# PhatStats_Slim_Enclosure_QTPY_PCB_v0_93.net
KiCad netlist of a schematic drawn in EAGLE
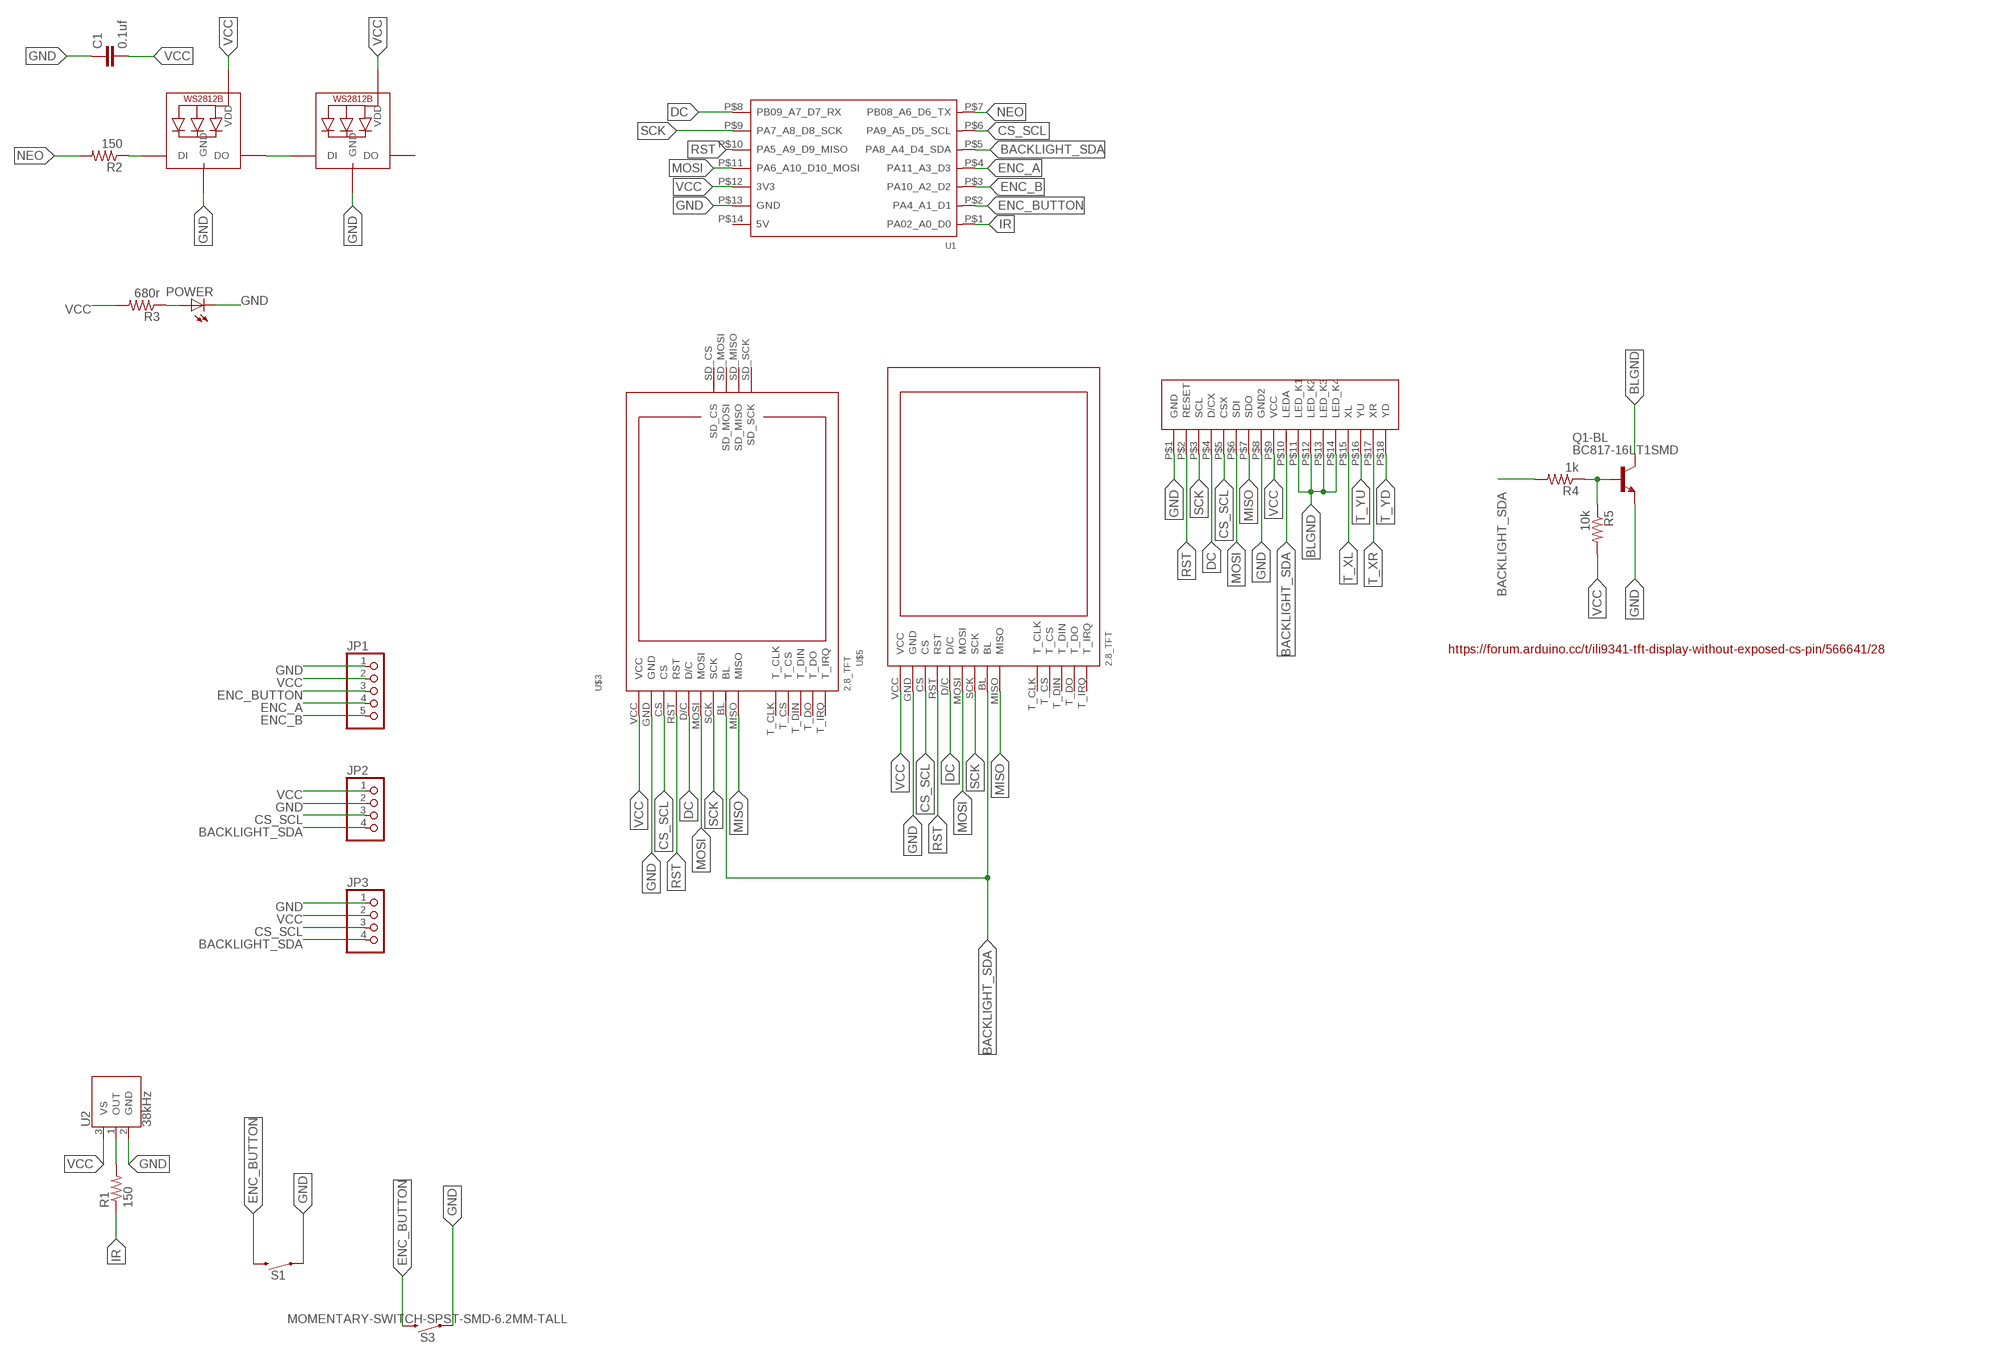
[diagram p0: schematic, sheet 1]

(export (version "E")
  (design (tool "Eeschema 10.0.6"))
  (components
    (comp (ref "0")
      (value "ILI9341-2.8")
      (footprint "eagle-import:ILI9341-2.8")
      (libsource (lib "eagle-import") (part "ILI9341-2.8"))
    )
    (comp (ref "C1")
      (value "0.1uf")
      (footprint "eagle-import:C1206")
      (libsource (lib "eagle-import") (part "C-EUC1206"))
    )
    (comp (ref "JP1")
      (value "PINHD-1X5")
      (footprint "eagle-import:1X05")
      (libsource (lib "eagle-import") (part "PINHD-1X5"))
    )
    (comp (ref "JP2")
      (value "PINHD-1X4")
      (footprint "eagle-import:1X04")
      (libsource (lib "eagle-import") (part "PINHD-1X4"))
    )
    (comp (ref "JP3")
      (value "PINHD-1X4")
      (footprint "eagle-import:1X04")
      (libsource (lib "eagle-import") (part "PINHD-1X4"))
    )
    (comp (ref "NEO1")
      (value "WS2812B5050")
      (footprint "eagle-import:WS2812B")
      (libsource (lib "eagle-import") (part "WS2812B5050"))
    )
    (comp (ref "NEO2")
      (value "WS2812B5050")
      (footprint "eagle-import:WS2812B")
      (libsource (lib "eagle-import") (part "WS2812B5050"))
    )
    (comp (ref "POWER")
      (value "LEDCHIPLED_1206")
      (footprint "eagle-import:CHIPLED_1206")
      (libsource (lib "eagle-import") (part "LEDCHIPLED_1206"))
    )
    (comp (ref "Q1-BL")
      (value "BC817-16LT1SMD")
      (footprint "eagle-import:SOT23-BEC")
      (libsource (lib "eagle-import") (part "BC817SMD-16LT1"))
    )
    (comp (ref "R1")
      (value "150")
      (footprint "eagle-import:M1206")
      (libsource (lib "eagle-import") (part "R-US_M1206"))
    )
    (comp (ref "R2")
      (value "150")
      (footprint "eagle-import:M1206")
      (libsource (lib "eagle-import") (part "R-US_M1206"))
    )
    (comp (ref "R3")
      (value "680r")
      (footprint "eagle-import:M1206")
      (libsource (lib "eagle-import") (part "R-US_M1206"))
    )
    (comp (ref "R4")
      (value "1k")
      (footprint "eagle-import:M1206")
      (libsource (lib "eagle-import") (part "R-US_M1206"))
    )
    (comp (ref "R5")
      (value "10k")
      (footprint "eagle-import:M1206")
      (libsource (lib "eagle-import") (part "R-US_M1206"))
    )
    (comp (ref "S1")
      (value "MOMENTARY-SWITCH-SPST-PTH-6.0MM")
      (footprint "eagle-import:TACTILE_SWITCH_PTH_6.0MM")
      (libsource (lib "eagle-import") (part "MOMENTARY-SWITCH-SPST-PTH-6.0MM"))
    )
    (comp (ref "S3")
      (value "MOMENTARY-SWITCH-SPST-SMD-6.2MM-TALL")
      (footprint "eagle-import:TACTILE_SWITCH_SMD_6.2MM_TALL")
      (libsource (lib "eagle-import") (part "MOMENTARY-SWITCH-SPST-SMD-6.2MM-TALL"))
    )
    (comp (ref "U$3")
      (value "2.8_TFT")
      (footprint "eagle-import:2.8_TFT")
      (libsource (lib "eagle-import") (part "2.8_TFT"))
    )
    (comp (ref "U$5")
      (value "2.8_TFT")
      (footprint "eagle-import:2.8_TFT")
      (libsource (lib "eagle-import") (part "TML_ili9341-2.8_tft-display_PinHeader only_2.8_TFT"))
    )
    (comp (ref "U1")
      (value "MOUDLE-SEEEDUINO-XIAO")
      (footprint "eagle-import:MOUDLE14P-2.54-21X17.8MM")
      (libsource (lib "eagle-import") (part "MOUDLE-SEEEDUINO-XIAO"))
    )
    (comp (ref "U2")
      (value "38kHz")
      (footprint "eagle-import:TSOP382")
      (libsource (lib "eagle-import") (part "TSOP38238"))
    )
  )
  (nets
    (net (code "1") (name "BACKLIGHT_SDA") (class "Default")
      (node (ref "0") (pin "P$10") (pinfunction "LEDA_P$10") (pintype "bidirectional"))
      (node (ref "JP2") (pin "4") (pinfunction "4_4") (pintype "passive"))
      (node (ref "JP3") (pin "4") (pinfunction "4_4") (pintype "passive"))
      (node (ref "R4") (pin "2") (pinfunction "2_2") (pintype "passive"))
      (node (ref "U$3") (pin "BL") (pinfunction "BL_BL") (pintype "bidirectional"))
      (node (ref "U$5") (pin "BL") (pinfunction "BL_BL") (pintype "bidirectional"))
      (node (ref "U1") (pin "P$5") (pinfunction "PA8_A4_D4_SDA_P$5") (pintype "bidirectional"))
    )
    (net (code "2") (name "BLGND") (class "Default")
      (node (ref "0") (pin "P$11") (pinfunction "LED_K1_P$11") (pintype "bidirectional"))
      (node (ref "0") (pin "P$12") (pinfunction "LED_K2_P$12") (pintype "bidirectional"))
      (node (ref "0") (pin "P$13") (pinfunction "LED_K3_P$13") (pintype "bidirectional"))
      (node (ref "0") (pin "P$14") (pinfunction "LED_K4_P$14") (pintype "bidirectional"))
      (node (ref "Q1-BL") (pin "C") (pinfunction "C_C") (pintype "passive"))
    )
    (net (code "3") (name "CS_SCL") (class "Default")
      (node (ref "0") (pin "P$5") (pinfunction "CSX_P$5") (pintype "bidirectional"))
      (node (ref "JP2") (pin "3") (pinfunction "3_3") (pintype "passive"))
      (node (ref "JP3") (pin "3") (pinfunction "3_3") (pintype "passive"))
      (node (ref "U$3") (pin "CS") (pinfunction "CS_CS") (pintype "bidirectional"))
      (node (ref "U$5") (pin "CS") (pinfunction "CS_CS") (pintype "bidirectional"))
      (node (ref "U1") (pin "P$6") (pinfunction "PA9_A5_D5_SCL_P$6") (pintype "bidirectional"))
    )
    (net (code "4") (name "DC") (class "Default")
      (node (ref "0") (pin "P$4") (pinfunction "D/CX_P$4") (pintype "bidirectional"))
      (node (ref "U$3") (pin "D/C") (pinfunction "D/C_D/C") (pintype "bidirectional"))
      (node (ref "U$5") (pin "D/C") (pinfunction "D/C_D/C") (pintype "bidirectional"))
      (node (ref "U1") (pin "P$8") (pinfunction "PB09_A7_D7_RX_P$8") (pintype "bidirectional"))
    )
    (net (code "5") (name "ENC_A") (class "Default")
      (node (ref "JP1") (pin "4") (pinfunction "4_4") (pintype "passive"))
      (node (ref "U1") (pin "P$4") (pinfunction "PA11_A3_D3_P$4") (pintype "bidirectional"))
    )
    (net (code "6") (name "ENC_B") (class "Default")
      (node (ref "JP1") (pin "5") (pinfunction "5_5") (pintype "passive"))
      (node (ref "U1") (pin "P$3") (pinfunction "PA10_A2_D2_P$3") (pintype "bidirectional"))
    )
    (net (code "7") (name "ENC_BUTTON") (class "Default")
      (node (ref "JP1") (pin "3") (pinfunction "3_3") (pintype "passive"))
      (node (ref "S1") (pin "3") (pinfunction "2_3") (pintype "passive"))
      (node (ref "S3") (pin "B2") (pinfunction "2_B2") (pintype "passive"))
      (node (ref "U1") (pin "P$2") (pinfunction "PA4_A1_D1_P$2") (pintype "bidirectional"))
    )
    (net (code "8") (name "GND") (class "Default")
      (node (ref "0") (pin "P$1") (pinfunction "GND_P$1") (pintype "bidirectional"))
      (node (ref "0") (pin "P$8") (pinfunction "GND2_P$8") (pintype "bidirectional"))
      (node (ref "C1") (pin "1") (pinfunction "1_1") (pintype "passive"))
      (node (ref "JP1") (pin "1") (pinfunction "1_1") (pintype "passive"))
      (node (ref "JP2") (pin "2") (pinfunction "2_2") (pintype "passive"))
      (node (ref "JP3") (pin "1") (pinfunction "1_1") (pintype "passive"))
      (node (ref "NEO1") (pin "3-GND") (pinfunction "GND_3-GND") (pintype "power_in"))
      (node (ref "NEO2") (pin "3-GND") (pinfunction "GND_3-GND") (pintype "power_in"))
      (node (ref "POWER") (pin "C") (pinfunction "C_C") (pintype "passive"))
      (node (ref "Q1-BL") (pin "E") (pinfunction "E_E") (pintype "passive"))
      (node (ref "S1") (pin "1") (pinfunction "1_1") (pintype "passive"))
      (node (ref "S3") (pin "A2") (pinfunction "1_A2") (pintype "passive"))
      (node (ref "U$3") (pin "GND") (pinfunction "GND_GND") (pintype "bidirectional"))
      (node (ref "U$5") (pin "GND") (pinfunction "GND_GND") (pintype "bidirectional"))
      (node (ref "U1") (pin "P$13") (pinfunction "GND_P$13") (pintype "bidirectional"))
      (node (ref "U2") (pin "2") (pinfunction "GND_2") (pintype "bidirectional"))
    )
    (net (code "9") (name "IR") (class "Default")
      (node (ref "R1") (pin "1") (pinfunction "1_1") (pintype "passive"))
      (node (ref "U1") (pin "P$1") (pinfunction "PA02_A0_D0_P$1") (pintype "bidirectional"))
    )
    (net (code "10") (name "MISO") (class "Default")
      (node (ref "0") (pin "P$7") (pinfunction "SDO_P$7") (pintype "bidirectional"))
      (node (ref "U$3") (pin "MISO") (pinfunction "MISO_MISO") (pintype "bidirectional"))
      (node (ref "U$5") (pin "MISO") (pinfunction "MISO_MISO") (pintype "bidirectional"))
    )
    (net (code "11") (name "MOSI") (class "Default")
      (node (ref "0") (pin "P$6") (pinfunction "SDI_P$6") (pintype "bidirectional"))
      (node (ref "U$3") (pin "MOSI") (pinfunction "MOSI_MOSI") (pintype "bidirectional"))
      (node (ref "U$5") (pin "MOSI") (pinfunction "MOSI_MOSI") (pintype "bidirectional"))
      (node (ref "U1") (pin "P$11") (pinfunction "PA6_A10_D10_MOSI_P$11") (pintype "bidirectional"))
    )
    (net (code "12") (name "NEO") (class "Default")
      (node (ref "R2") (pin "2") (pinfunction "2_2") (pintype "passive"))
      (node (ref "U1") (pin "P$7") (pinfunction "PB08_A6_D6_TX_P$7") (pintype "bidirectional"))
    )
    (net (code "13") (name "Net-(NEO1-DI)") (class "Default")
      (node (ref "NEO1") (pin "4-DIN") (pinfunction "DI_4-DIN") (pintype "input"))
      (node (ref "R2") (pin "1") (pinfunction "1_1") (pintype "passive"))
    )
    (net (code "14") (name "Net-(NEO1-DO)") (class "Default")
      (node (ref "NEO1") (pin "2-DOUT") (pinfunction "DO_2-DOUT") (pintype "output"))
      (node (ref "NEO2") (pin "4-DIN") (pinfunction "DI_4-DIN") (pintype "input"))
    )
    (net (code "15") (name "Net-(POWER-PadA)") (class "Default")
      (node (ref "POWER") (pin "A") (pinfunction "A_A") (pintype "passive"))
      (node (ref "R3") (pin "1") (pinfunction "1_1") (pintype "passive"))
    )
    (net (code "16") (name "Net-(Q1-BL-PadB)") (class "Default")
      (node (ref "Q1-BL") (pin "B") (pinfunction "B_B") (pintype "passive"))
      (node (ref "R4") (pin "1") (pinfunction "1_1") (pintype "passive"))
      (node (ref "R5") (pin "1") (pinfunction "1_1") (pintype "passive"))
    )
    (net (code "17") (name "Net-(U2-OUT)") (class "Default")
      (node (ref "R1") (pin "2") (pinfunction "2_2") (pintype "passive"))
      (node (ref "U2") (pin "1") (pinfunction "OUT_1") (pintype "bidirectional"))
    )
    (net (code "18") (name "RST") (class "Default")
      (node (ref "0") (pin "P$2") (pinfunction "RESET_P$2") (pintype "bidirectional"))
      (node (ref "U$3") (pin "RST") (pinfunction "RST_RST") (pintype "bidirectional"))
      (node (ref "U$5") (pin "RST") (pinfunction "RST_RST") (pintype "bidirectional"))
      (node (ref "U1") (pin "P$10") (pinfunction "PA5_A9_D9_MISO_P$10") (pintype "bidirectional"))
    )
    (net (code "19") (name "SCK") (class "Default")
      (node (ref "0") (pin "P$3") (pinfunction "SCL_P$3") (pintype "bidirectional"))
      (node (ref "U$3") (pin "SCK") (pinfunction "SCK_SCK") (pintype "bidirectional"))
      (node (ref "U$5") (pin "SCK") (pinfunction "SCK_SCK") (pintype "bidirectional"))
      (node (ref "U1") (pin "P$9") (pinfunction "PA7_A8_D8_SCK_P$9") (pintype "bidirectional"))
    )
    (net (code "20") (name "T_XL") (class "Default")
      (node (ref "0") (pin "P$15") (pinfunction "XL_P$15") (pintype "bidirectional"))
    )
    (net (code "21") (name "T_XR") (class "Default")
      (node (ref "0") (pin "P$17") (pinfunction "XR_P$17") (pintype "bidirectional"))
    )
    (net (code "22") (name "T_YD") (class "Default")
      (node (ref "0") (pin "P$18") (pinfunction "YD_P$18") (pintype "bidirectional"))
    )
    (net (code "23") (name "T_YU") (class "Default")
      (node (ref "0") (pin "P$16") (pinfunction "YU_P$16") (pintype "bidirectional"))
    )
    (net (code "24") (name "VCC") (class "Default")
      (node (ref "0") (pin "P$9") (pinfunction "VCC_P$9") (pintype "bidirectional"))
      (node (ref "C1") (pin "2") (pinfunction "2_2") (pintype "passive"))
      (node (ref "JP1") (pin "2") (pinfunction "2_2") (pintype "passive"))
      (node (ref "JP2") (pin "1") (pinfunction "1_1") (pintype "passive"))
      (node (ref "JP3") (pin "2") (pinfunction "2_2") (pintype "passive"))
      (node (ref "NEO1") (pin "1-VDD") (pinfunction "VDD_1-VDD") (pintype "power_in"))
      (node (ref "NEO2") (pin "1-VDD") (pinfunction "VDD_1-VDD") (pintype "power_in"))
      (node (ref "R3") (pin "2") (pinfunction "2_2") (pintype "passive"))
      (node (ref "R5") (pin "2") (pinfunction "2_2") (pintype "passive"))
      (node (ref "U$3") (pin "VCC") (pinfunction "VCC_VCC") (pintype "bidirectional"))
      (node (ref "U$5") (pin "VCC") (pinfunction "VCC_VCC") (pintype "bidirectional"))
      (node (ref "U1") (pin "P$12") (pinfunction "3V3_P$12") (pintype "bidirectional"))
      (node (ref "U2") (pin "3") (pinfunction "VS_3") (pintype "bidirectional"))
    )
    (net (code "25") (name "unconnected-(NEO2-DO-Pad2-DOUT)") (class "Default")
      (node (ref "NEO2") (pin "2-DOUT") (pinfunction "DO_2-DOUT") (pintype "output"))
    )
    (net (code "26") (name "unconnected-(U$3-PadSD_CS)") (class "Default")
      (node (ref "U$3") (pin "SD_CS") (pinfunction "SD_CS_SD_CS") (pintype "bidirectional"))
    )
    (net (code "27") (name "unconnected-(U$3-PadSD_MISO)") (class "Default")
      (node (ref "U$3") (pin "SD_MISO") (pinfunction "SD_MISO_SD_MISO") (pintype "bidirectional"))
    )
    (net (code "28") (name "unconnected-(U$3-PadSD_MOSI)") (class "Default")
      (node (ref "U$3") (pin "SD_MOSI") (pinfunction "SD_MOSI_SD_MOSI") (pintype "bidirectional"))
    )
    (net (code "29") (name "unconnected-(U$3-PadSD_SCK)") (class "Default")
      (node (ref "U$3") (pin "SD_SCK") (pinfunction "SD_SCK_SD_SCK") (pintype "bidirectional"))
    )
    (net (code "30") (name "unconnected-(U$3-PadT_CLK)") (class "Default")
      (node (ref "U$3") (pin "T_CLK") (pinfunction "T_CLK_T_CLK") (pintype "bidirectional"))
    )
    (net (code "31") (name "unconnected-(U$3-PadT_CS)") (class "Default")
      (node (ref "U$3") (pin "T_CS") (pinfunction "T_CS_T_CS") (pintype "bidirectional"))
    )
    (net (code "32") (name "unconnected-(U$3-PadT_DIN)") (class "Default")
      (node (ref "U$3") (pin "T_DIN") (pinfunction "T_DIN_T_DIN") (pintype "bidirectional"))
    )
    (net (code "33") (name "unconnected-(U$3-PadT_DO)") (class "Default")
      (node (ref "U$3") (pin "T_DO") (pinfunction "T_DO_T_DO") (pintype "bidirectional"))
    )
    (net (code "34") (name "unconnected-(U$3-PadT_IRQ)") (class "Default")
      (node (ref "U$3") (pin "T_IRQ") (pinfunction "T_IRQ_T_IRQ") (pintype "bidirectional"))
    )
    (net (code "35") (name "unconnected-(U$5-PadT_CLK)") (class "Default")
      (node (ref "U$5") (pin "T_CLK") (pinfunction "T_CLK_T_CLK") (pintype "bidirectional"))
    )
    (net (code "36") (name "unconnected-(U$5-PadT_CS)") (class "Default")
      (node (ref "U$5") (pin "T_CS") (pinfunction "T_CS_T_CS") (pintype "bidirectional"))
    )
    (net (code "37") (name "unconnected-(U$5-PadT_DIN)") (class "Default")
      (node (ref "U$5") (pin "T_DIN") (pinfunction "T_DIN_T_DIN") (pintype "bidirectional"))
    )
    (net (code "38") (name "unconnected-(U$5-PadT_DO)") (class "Default")
      (node (ref "U$5") (pin "T_DO") (pinfunction "T_DO_T_DO") (pintype "bidirectional"))
    )
    (net (code "39") (name "unconnected-(U$5-PadT_IRQ)") (class "Default")
      (node (ref "U$5") (pin "T_IRQ") (pinfunction "T_IRQ_T_IRQ") (pintype "bidirectional"))
    )
    (net (code "40") (name "unconnected-(U1-5V-PadP$14)") (class "Default")
      (node (ref "U1") (pin "P$14") (pinfunction "5V_P$14") (pintype "bidirectional"))
    )
  )
)
